# 2-SOM_Interface.net
KiCad netlist of a schematic drawn in Altium Designer
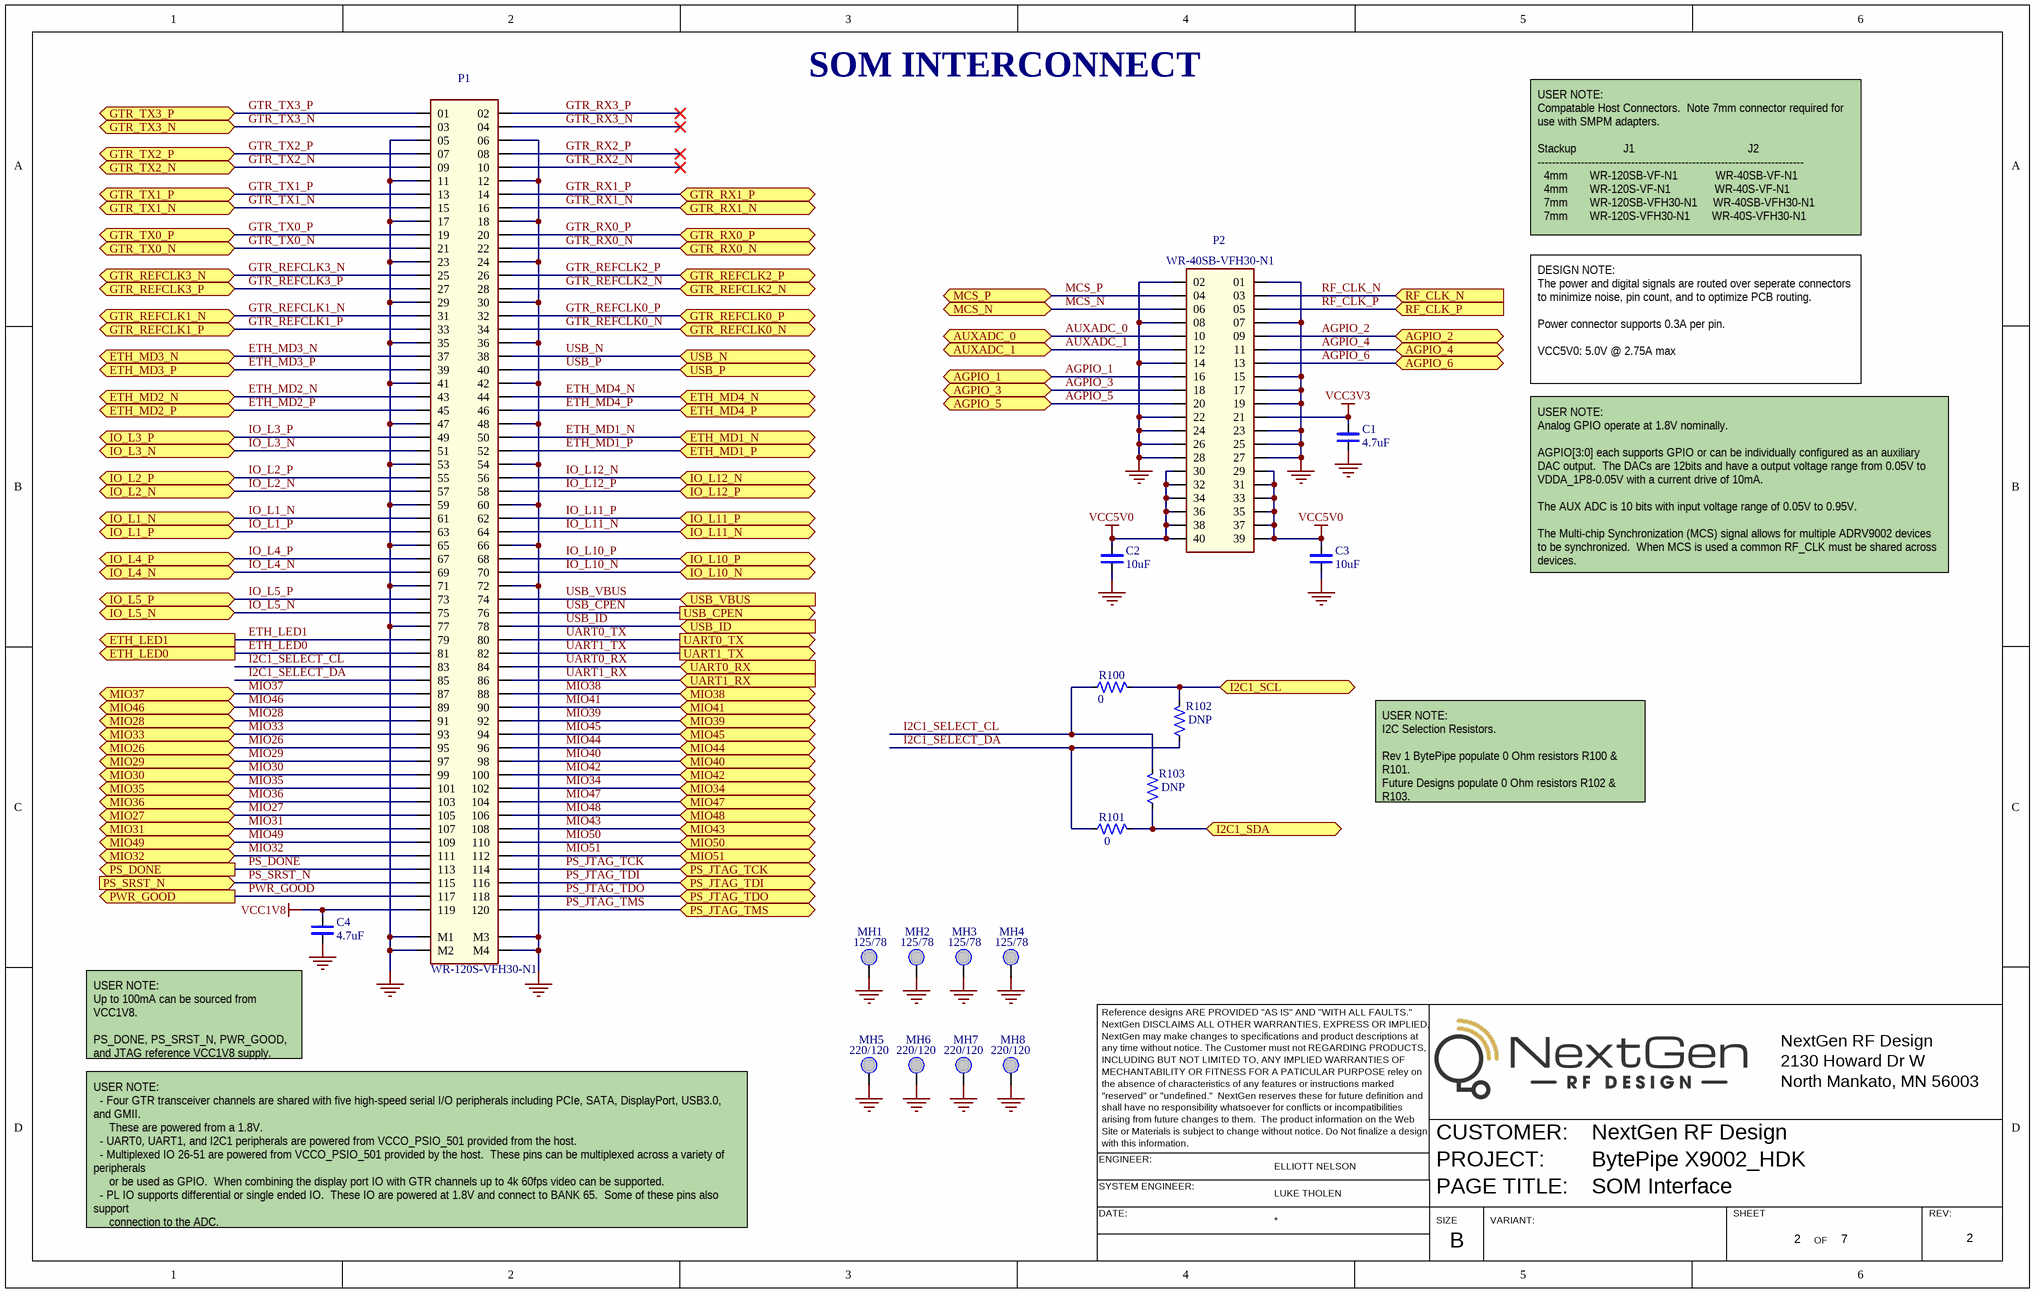
[diagram p0: 2-SOM Interface.SchDoc]

(export (version "E")
  (design (tool "Eeschema 10.0.6"))
  (components
    (comp (ref "C1")
      (value "4.7uF")
      (footprint "SM/0402/CAP")
      (description "CAP CER 4.7UF 10V X5R 0402")
      (fields (field (name "Comment") "CAP_CERAMIC_0402"))
      (libsource (lib "NextGenRF_Symbols_SMT") (part "CAP_CERAMIC_0402"))
    )
    (comp (ref "C2")
      (value "10uF")
      (footprint "SM/0402/CAP")
      (description "10µF ±20% 10V Ceramic Capacitor X5R 0402 (1005 Metric)")
      (fields (field (name "Comment") "CAP_CERAMIC_0402"))
      (libsource (lib "NextGenRF_Symbols_SMT") (part "CAP_CERAMIC_0402"))
    )
    (comp (ref "C3")
      (value "10uF")
      (footprint "SM/0402/CAP")
      (description "10µF ±20% 10V Ceramic Capacitor X5R 0402 (1005 Metric)")
      (fields (field (name "Comment") "CAP_CERAMIC_0402"))
      (libsource (lib "NextGenRF_Symbols_SMT") (part "CAP_CERAMIC_0402"))
    )
    (comp (ref "C4")
      (value "4.7uF")
      (footprint "SM/0402/CAP")
      (description "CAP CER 4.7UF 10V X5R 0402")
      (fields (field (name "Comment") "CAP_CERAMIC_0402"))
      (libsource (lib "NextGenRF_Symbols_SMT") (part "CAP_CERAMIC_0402"))
    )
    (comp (ref "MH1")
      (value "HOLE_PTH_125/78")
      (footprint "NGRF_Mechanical_Footprints:MTG125/78")
      (description "125 mil pad / 78 mil hole")
      (libsource (lib "NextGenRF_Symbols_MECH") (part "HOLE_PTH_125/78"))
    )
    (comp (ref "MH2")
      (value "HOLE_PTH_125/78")
      (footprint "NGRF_Mechanical_Footprints:MTG125/78")
      (description "125 mil pad / 78 mil hole")
      (libsource (lib "NextGenRF_Symbols_MECH") (part "HOLE_PTH_125/78"))
    )
    (comp (ref "MH3")
      (value "HOLE_PTH_125/78")
      (footprint "NGRF_Mechanical_Footprints:MTG125/78")
      (description "125 mil pad / 78 mil hole")
      (libsource (lib "NextGenRF_Symbols_MECH") (part "HOLE_PTH_125/78"))
    )
    (comp (ref "MH4")
      (value "HOLE_PTH_125/78")
      (footprint "NGRF_Mechanical_Footprints:MTG125/78")
      (description "125 mil pad / 78 mil hole")
      (libsource (lib "NextGenRF_Symbols_MECH") (part "HOLE_PTH_125/78"))
    )
    (comp (ref "MH5")
      (value "HOLE_PTH_220/120")
      (footprint "MTG220/120")
      (description "220 mil pad / 120 mil hole (#4 Pan Head Screw)")
      (libsource (lib "NextGenRF_Symbols_MECH") (part "HOLE_PTH_220/120"))
    )
    (comp (ref "MH6")
      (value "HOLE_PTH_220/120")
      (footprint "MTG220/120")
      (description "220 mil pad / 120 mil hole (#4 Pan Head Screw)")
      (libsource (lib "NextGenRF_Symbols_MECH") (part "HOLE_PTH_220/120"))
    )
    (comp (ref "MH7")
      (value "HOLE_PTH_220/120")
      (footprint "MTG220/120")
      (description "220 mil pad / 120 mil hole (#4 Pan Head Screw)")
      (libsource (lib "NextGenRF_Symbols_MECH") (part "HOLE_PTH_220/120"))
    )
    (comp (ref "MH8")
      (value "HOLE_PTH_220/120")
      (footprint "MTG220/120")
      (description "220 mil pad / 120 mil hole (#4 Pan Head Screw)")
      (libsource (lib "NextGenRF_Symbols_MECH") (part "HOLE_PTH_220/120"))
    )
    (comp (ref "P1")
      (value "WR-120S-VFH30-N1")
      (footprint "SM/CON/JAE/WR-120S-VFH30-N1")
      (description "0.5 mm pitch, 120 Position Connector Receptacle, Center Strip Contacts Surface Mount Gold.")
      (fields (field (name "Comment") "WR-120S-VFH30-N1‎"))
      (libsource (lib "NextGenRF_Symbols_SMT") (part "CON_JAE_WR-120S-VFH30-N1"))
    )
    (comp (ref "P2")
      (value "WR-40SB-VFH30-N1")
      (footprint "SM/CON/JAE/WR-40SB-VFH30-N1")
      (fields (field (name "Comment") "WR-40SB-VFH30-N1‎"))
      (libsource (lib "NextGenRF_Symbols_SMT") (part "CON_JAE_WR-40SB-VFH30-N1"))
    )
    (comp (ref "R100")
      (value "0")
      (footprint "SM/0402/RES")
      (description "RES SMD 0 OHM JUMPER 1/10W 0402")
      (fields (field (name "Comment") "RES_0402_A"))
      (libsource (lib "NextGenRF_Symbols_SMT") (part "RES_0402_A"))
    )
    (comp (ref "R101")
      (value "0")
      (footprint "SM/0402/RES")
      (description "RES SMD 0 OHM JUMPER 1/10W 0402")
      (fields (field (name "Comment") "RES_0402_A"))
      (libsource (lib "NextGenRF_Symbols_SMT") (part "RES_0402_A"))
    )
    (comp (ref "R102")
      (value "DNP")
      (footprint "SM/0402/RES")
      (fields (field (name "Comment") "RES_0402_A"))
      (libsource (lib "NextGenRF_Symbols_SMT") (part "RES_0402_A"))
    )
    (comp (ref "R103")
      (value "DNP")
      (footprint "SM/0402/RES")
      (fields (field (name "Comment") "RES_0402_A"))
      (libsource (lib "NextGenRF_Symbols_SMT") (part "RES_0402_A"))
    )
  )
  (nets
    (net (code "1") (name "/AGPIO_1") (class "Default")
      (node (ref "P2") (pin "16") (pinfunction "16_16") (pintype "passive"))
    )
    (net (code "2") (name "/AGPIO_2") (class "Default")
      (node (ref "P2") (pin "09") (pinfunction "09_09") (pintype "passive"))
    )
    (net (code "3") (name "/AGPIO_3") (class "Default")
      (node (ref "P2") (pin "18") (pinfunction "18_18") (pintype "passive"))
    )
    (net (code "4") (name "/AGPIO_4") (class "Default")
      (node (ref "P2") (pin "11") (pinfunction "11_11") (pintype "passive"))
    )
    (net (code "5") (name "/AGPIO_5") (class "Default")
      (node (ref "P2") (pin "20") (pinfunction "20_20") (pintype "passive"))
    )
    (net (code "6") (name "/AGPIO_6") (class "Default")
      (node (ref "P2") (pin "13") (pinfunction "13_13") (pintype "passive"))
    )
    (net (code "7") (name "/AUXADC_0") (class "Default")
      (node (ref "P2") (pin "10") (pinfunction "10_10") (pintype "passive"))
    )
    (net (code "8") (name "/AUXADC_1") (class "Default")
      (node (ref "P2") (pin "12") (pinfunction "12_12") (pintype "passive"))
    )
    (net (code "9") (name "/ETH_LED0") (class "Default")
      (node (ref "P1") (pin "81") (pinfunction "81_81") (pintype "passive"))
    )
    (net (code "10") (name "/ETH_LED1") (class "Default")
      (node (ref "P1") (pin "79") (pinfunction "79_79") (pintype "passive"))
    )
    (net (code "11") (name "/ETH_MD1_N") (class "Default")
      (node (ref "P1") (pin "50") (pinfunction "50_50") (pintype "passive"))
    )
    (net (code "12") (name "/ETH_MD1_P") (class "Default")
      (node (ref "P1") (pin "52") (pinfunction "52_52") (pintype "passive"))
    )
    (net (code "13") (name "/ETH_MD2_N") (class "Default")
      (node (ref "P1") (pin "43") (pinfunction "43_43") (pintype "passive"))
    )
    (net (code "14") (name "/ETH_MD2_P") (class "Default")
      (node (ref "P1") (pin "45") (pinfunction "45_45") (pintype "passive"))
    )
    (net (code "15") (name "/ETH_MD3_N") (class "Default")
      (node (ref "P1") (pin "37") (pinfunction "37_37") (pintype "passive"))
    )
    (net (code "16") (name "/ETH_MD3_P") (class "Default")
      (node (ref "P1") (pin "39") (pinfunction "39_39") (pintype "passive"))
    )
    (net (code "17") (name "/ETH_MD4_N") (class "Default")
      (node (ref "P1") (pin "44") (pinfunction "44_44") (pintype "passive"))
    )
    (net (code "18") (name "/ETH_MD4_P") (class "Default")
      (node (ref "P1") (pin "46") (pinfunction "46_46") (pintype "passive"))
    )
    (net (code "19") (name "/GTR_REFCLK0_N") (class "Default")
      (node (ref "P1") (pin "34") (pinfunction "34_34") (pintype "passive"))
    )
    (net (code "20") (name "/GTR_REFCLK0_P") (class "Default")
      (node (ref "P1") (pin "32") (pinfunction "32_32") (pintype "passive"))
    )
    (net (code "21") (name "/GTR_REFCLK1_N") (class "Default")
      (node (ref "P1") (pin "31") (pinfunction "31_31") (pintype "passive"))
    )
    (net (code "22") (name "/GTR_REFCLK1_P") (class "Default")
      (node (ref "P1") (pin "33") (pinfunction "33_33") (pintype "passive"))
    )
    (net (code "23") (name "/GTR_REFCLK2_N") (class "Default")
      (node (ref "P1") (pin "28") (pinfunction "28_28") (pintype "passive"))
    )
    (net (code "24") (name "/GTR_REFCLK2_P") (class "Default")
      (node (ref "P1") (pin "26") (pinfunction "26_26") (pintype "passive"))
    )
    (net (code "25") (name "/GTR_REFCLK3_N") (class "Default")
      (node (ref "P1") (pin "25") (pinfunction "25_25") (pintype "passive"))
    )
    (net (code "26") (name "/GTR_REFCLK3_P") (class "Default")
      (node (ref "P1") (pin "27") (pinfunction "27_27") (pintype "passive"))
    )
    (net (code "27") (name "/GTR_RX0_N") (class "Default")
      (node (ref "P1") (pin "22") (pinfunction "22_22") (pintype "passive"))
    )
    (net (code "28") (name "/GTR_RX0_P") (class "Default")
      (node (ref "P1") (pin "20") (pinfunction "20_20") (pintype "passive"))
    )
    (net (code "29") (name "/GTR_RX1_N") (class "Default")
      (node (ref "P1") (pin "16") (pinfunction "16_16") (pintype "passive"))
    )
    (net (code "30") (name "/GTR_RX1_P") (class "Default")
      (node (ref "P1") (pin "14") (pinfunction "14_14") (pintype "passive"))
    )
    (net (code "31") (name "/GTR_RX2_N") (class "Default")
      (node (ref "P1") (pin "10") (pinfunction "10_10") (pintype "passive+no_connect"))
    )
    (net (code "32") (name "/GTR_RX2_P") (class "Default")
      (node (ref "P1") (pin "08") (pinfunction "08_08") (pintype "passive+no_connect"))
    )
    (net (code "33") (name "/GTR_RX3_N") (class "Default")
      (node (ref "P1") (pin "04") (pinfunction "04_04") (pintype "passive+no_connect"))
    )
    (net (code "34") (name "/GTR_RX3_P") (class "Default")
      (node (ref "P1") (pin "02") (pinfunction "02_02") (pintype "passive+no_connect"))
    )
    (net (code "35") (name "/GTR_TX0_N") (class "Default")
      (node (ref "P1") (pin "21") (pinfunction "21_21") (pintype "passive"))
    )
    (net (code "36") (name "/GTR_TX0_P") (class "Default")
      (node (ref "P1") (pin "19") (pinfunction "19_19") (pintype "passive"))
    )
    (net (code "37") (name "/GTR_TX1_N") (class "Default")
      (node (ref "P1") (pin "15") (pinfunction "15_15") (pintype "passive"))
    )
    (net (code "38") (name "/GTR_TX1_P") (class "Default")
      (node (ref "P1") (pin "13") (pinfunction "13_13") (pintype "passive"))
    )
    (net (code "39") (name "/GTR_TX2_N") (class "Default")
      (node (ref "P1") (pin "09") (pinfunction "09_09") (pintype "passive"))
    )
    (net (code "40") (name "/GTR_TX2_P") (class "Default")
      (node (ref "P1") (pin "07") (pinfunction "07_07") (pintype "passive"))
    )
    (net (code "41") (name "/GTR_TX3_N") (class "Default")
      (node (ref "P1") (pin "03") (pinfunction "03_03") (pintype "passive"))
    )
    (net (code "42") (name "/GTR_TX3_P") (class "Default")
      (node (ref "P1") (pin "01") (pinfunction "01_01") (pintype "passive"))
    )
    (net (code "43") (name "/I2C1_SCL") (class "Default")
      (node (ref "R100") (pin "1") (pinfunction "1_1") (pintype "passive"))
      (node (ref "R102") (pin "1") (pinfunction "1_1") (pintype "passive"))
    )
    (net (code "44") (name "/I2C1_SDA") (class "Default")
      (node (ref "R101") (pin "1") (pinfunction "1_1") (pintype "passive"))
      (node (ref "R103") (pin "2") (pinfunction "2_2") (pintype "passive"))
    )
    (net (code "45") (name "/I2C1_SELECT_CL") (class "Default")
      (node (ref "P1") (pin "83") (pinfunction "83_83") (pintype "passive"))
      (node (ref "R100") (pin "2") (pinfunction "2_2") (pintype "passive"))
      (node (ref "R103") (pin "1") (pinfunction "1_1") (pintype "passive"))
    )
    (net (code "46") (name "/I2C1_SELECT_DA") (class "Default")
      (node (ref "P1") (pin "85") (pinfunction "85_85") (pintype "passive"))
      (node (ref "R101") (pin "2") (pinfunction "2_2") (pintype "passive"))
      (node (ref "R102") (pin "2") (pinfunction "2_2") (pintype "passive"))
    )
    (net (code "47") (name "/IO_L1_N") (class "Default")
      (node (ref "P1") (pin "61") (pinfunction "61_61") (pintype "passive"))
    )
    (net (code "48") (name "/IO_L1_P") (class "Default")
      (node (ref "P1") (pin "63") (pinfunction "63_63") (pintype "passive"))
    )
    (net (code "49") (name "/IO_L2_N") (class "Default")
      (node (ref "P1") (pin "57") (pinfunction "57_57") (pintype "passive"))
    )
    (net (code "50") (name "/IO_L2_P") (class "Default")
      (node (ref "P1") (pin "55") (pinfunction "55_55") (pintype "passive"))
    )
    (net (code "51") (name "/IO_L3_N") (class "Default")
      (node (ref "P1") (pin "51") (pinfunction "51_51") (pintype "passive"))
    )
    (net (code "52") (name "/IO_L3_P") (class "Default")
      (node (ref "P1") (pin "49") (pinfunction "49_49") (pintype "passive"))
    )
    (net (code "53") (name "/IO_L4_N") (class "Default")
      (node (ref "P1") (pin "69") (pinfunction "69_69") (pintype "passive"))
    )
    (net (code "54") (name "/IO_L4_P") (class "Default")
      (node (ref "P1") (pin "67") (pinfunction "67_67") (pintype "passive"))
    )
    (net (code "55") (name "/IO_L5_N") (class "Default")
      (node (ref "P1") (pin "75") (pinfunction "75_75") (pintype "passive"))
    )
    (net (code "56") (name "/IO_L5_P") (class "Default")
      (node (ref "P1") (pin "73") (pinfunction "73_73") (pintype "passive"))
    )
    (net (code "57") (name "/IO_L10_N") (class "Default")
      (node (ref "P1") (pin "70") (pinfunction "70_70") (pintype "passive"))
    )
    (net (code "58") (name "/IO_L10_P") (class "Default")
      (node (ref "P1") (pin "68") (pinfunction "68_68") (pintype "passive"))
    )
    (net (code "59") (name "/IO_L11_N") (class "Default")
      (node (ref "P1") (pin "64") (pinfunction "64_64") (pintype "passive"))
    )
    (net (code "60") (name "/IO_L11_P") (class "Default")
      (node (ref "P1") (pin "62") (pinfunction "62_62") (pintype "passive"))
    )
    (net (code "61") (name "/IO_L12_N") (class "Default")
      (node (ref "P1") (pin "56") (pinfunction "56_56") (pintype "passive"))
    )
    (net (code "62") (name "/IO_L12_P") (class "Default")
      (node (ref "P1") (pin "58") (pinfunction "58_58") (pintype "passive"))
    )
    (net (code "63") (name "/MCS_N") (class "Default")
      (node (ref "P2") (pin "06") (pinfunction "06_06") (pintype "passive"))
    )
    (net (code "64") (name "/MCS_P") (class "Default")
      (node (ref "P2") (pin "04") (pinfunction "04_04") (pintype "passive"))
    )
    (net (code "65") (name "/MIO26") (class "Default")
      (node (ref "P1") (pin "95") (pinfunction "95_95") (pintype "passive"))
    )
    (net (code "66") (name "/MIO27") (class "Default")
      (node (ref "P1") (pin "105") (pinfunction "105_105") (pintype "passive"))
    )
    (net (code "67") (name "/MIO28") (class "Default")
      (node (ref "P1") (pin "91") (pinfunction "91_91") (pintype "passive"))
    )
    (net (code "68") (name "/MIO29") (class "Default")
      (node (ref "P1") (pin "97") (pinfunction "97_97") (pintype "passive"))
    )
    (net (code "69") (name "/MIO30") (class "Default")
      (node (ref "P1") (pin "99") (pinfunction "99_99") (pintype "passive"))
    )
    (net (code "70") (name "/MIO31") (class "Default")
      (node (ref "P1") (pin "107") (pinfunction "107_107") (pintype "passive"))
    )
    (net (code "71") (name "/MIO32") (class "Default")
      (node (ref "P1") (pin "111") (pinfunction "111_111") (pintype "passive"))
    )
    (net (code "72") (name "/MIO33") (class "Default")
      (node (ref "P1") (pin "93") (pinfunction "93_93") (pintype "passive"))
    )
    (net (code "73") (name "/MIO34") (class "Default")
      (node (ref "P1") (pin "102") (pinfunction "102_102") (pintype "passive"))
    )
    (net (code "74") (name "/MIO35") (class "Default")
      (node (ref "P1") (pin "101") (pinfunction "101_101") (pintype "passive"))
    )
    (net (code "75") (name "/MIO36") (class "Default")
      (node (ref "P1") (pin "103") (pinfunction "103_103") (pintype "passive"))
    )
    (net (code "76") (name "/MIO37") (class "Default")
      (node (ref "P1") (pin "87") (pinfunction "87_87") (pintype "passive"))
    )
    (net (code "77") (name "/MIO38") (class "Default")
      (node (ref "P1") (pin "88") (pinfunction "88_88") (pintype "passive"))
    )
    (net (code "78") (name "/MIO39") (class "Default")
      (node (ref "P1") (pin "92") (pinfunction "92_92") (pintype "passive"))
    )
    (net (code "79") (name "/MIO40") (class "Default")
      (node (ref "P1") (pin "98") (pinfunction "98_98") (pintype "passive"))
    )
    (net (code "80") (name "/MIO41") (class "Default")
      (node (ref "P1") (pin "90") (pinfunction "90_90") (pintype "passive"))
    )
    (net (code "81") (name "/MIO42") (class "Default")
      (node (ref "P1") (pin "100") (pinfunction "100_100") (pintype "passive"))
    )
    (net (code "82") (name "/MIO43") (class "Default")
      (node (ref "P1") (pin "108") (pinfunction "108_108") (pintype "passive"))
    )
    (net (code "83") (name "/MIO44") (class "Default")
      (node (ref "P1") (pin "96") (pinfunction "96_96") (pintype "passive"))
    )
    (net (code "84") (name "/MIO45") (class "Default")
      (node (ref "P1") (pin "94") (pinfunction "94_94") (pintype "passive"))
    )
    (net (code "85") (name "/MIO46") (class "Default")
      (node (ref "P1") (pin "89") (pinfunction "89_89") (pintype "passive"))
    )
    (net (code "86") (name "/MIO47") (class "Default")
      (node (ref "P1") (pin "104") (pinfunction "104_104") (pintype "passive"))
    )
    (net (code "87") (name "/MIO48") (class "Default")
      (node (ref "P1") (pin "106") (pinfunction "106_106") (pintype "passive"))
    )
    (net (code "88") (name "/MIO49") (class "Default")
      (node (ref "P1") (pin "109") (pinfunction "109_109") (pintype "passive"))
    )
    (net (code "89") (name "/MIO50") (class "Default")
      (node (ref "P1") (pin "110") (pinfunction "110_110") (pintype "passive"))
    )
    (net (code "90") (name "/MIO51") (class "Default")
      (node (ref "P1") (pin "112") (pinfunction "112_112") (pintype "passive"))
    )
    (net (code "91") (name "/PS_DONE") (class "Default")
      (node (ref "P1") (pin "113") (pinfunction "113_113") (pintype "passive"))
    )
    (net (code "92") (name "/PS_JTAG_TCK") (class "Default")
      (node (ref "P1") (pin "114") (pinfunction "114_114") (pintype "passive"))
    )
    (net (code "93") (name "/PS_JTAG_TDI") (class "Default")
      (node (ref "P1") (pin "116") (pinfunction "116_116") (pintype "passive"))
    )
    (net (code "94") (name "/PS_JTAG_TDO") (class "Default")
      (node (ref "P1") (pin "118") (pinfunction "118_118") (pintype "passive"))
    )
    (net (code "95") (name "/PS_JTAG_TMS") (class "Default")
      (node (ref "P1") (pin "120") (pinfunction "120_120") (pintype "passive"))
    )
    (net (code "96") (name "/PS_SRST_N") (class "Default")
      (node (ref "P1") (pin "115") (pinfunction "115_115") (pintype "passive"))
    )
    (net (code "97") (name "/PWR_GOOD") (class "Default")
      (node (ref "P1") (pin "117") (pinfunction "117_117") (pintype "passive"))
    )
    (net (code "98") (name "/RF_CLK_N") (class "Default")
      (node (ref "P2") (pin "03") (pinfunction "03_03") (pintype "passive"))
    )
    (net (code "99") (name "/RF_CLK_P") (class "Default")
      (node (ref "P2") (pin "05") (pinfunction "05_05") (pintype "passive"))
    )
    (net (code "100") (name "/UART0_RX") (class "Default")
      (node (ref "P1") (pin "84") (pinfunction "84_84") (pintype "passive"))
    )
    (net (code "101") (name "/UART0_TX") (class "Default")
      (node (ref "P1") (pin "80") (pinfunction "80_80") (pintype "passive"))
    )
    (net (code "102") (name "/UART1_RX") (class "Default")
      (node (ref "P1") (pin "86") (pinfunction "86_86") (pintype "passive"))
    )
    (net (code "103") (name "/UART1_TX") (class "Default")
      (node (ref "P1") (pin "82") (pinfunction "82_82") (pintype "passive"))
    )
    (net (code "104") (name "/USB_CPEN") (class "Default")
      (node (ref "P1") (pin "76") (pinfunction "76_76") (pintype "passive"))
    )
    (net (code "105") (name "/USB_ID") (class "Default")
      (node (ref "P1") (pin "78") (pinfunction "78_78") (pintype "passive"))
    )
    (net (code "106") (name "/USB_N") (class "Default")
      (node (ref "P1") (pin "38") (pinfunction "38_38") (pintype "passive"))
    )
    (net (code "107") (name "/USB_P") (class "Default")
      (node (ref "P1") (pin "40") (pinfunction "40_40") (pintype "passive"))
    )
    (net (code "108") (name "/USB_VBUS") (class "Default")
      (node (ref "P1") (pin "74") (pinfunction "74_74") (pintype "passive"))
    )
    (net (code "109") (name "GND") (class "Default")
      (node (ref "C1") (pin "2") (pinfunction "N2_2") (pintype "passive"))
      (node (ref "C2") (pin "2") (pinfunction "N2_2") (pintype "passive"))
      (node (ref "C3") (pin "2") (pinfunction "N2_2") (pintype "passive"))
      (node (ref "C4") (pin "2") (pinfunction "N2_2") (pintype "passive"))
      (node (ref "MH1") (pin "1") (pinfunction "N1_1") (pintype "passive"))
      (node (ref "MH2") (pin "1") (pinfunction "N1_1") (pintype "passive"))
      (node (ref "MH3") (pin "1") (pinfunction "N1_1") (pintype "passive"))
      (node (ref "MH4") (pin "1") (pinfunction "N1_1") (pintype "passive"))
      (node (ref "MH5") (pin "1") (pinfunction "N1_1") (pintype "passive"))
      (node (ref "MH6") (pin "1") (pinfunction "N1_1") (pintype "passive"))
      (node (ref "MH7") (pin "1") (pinfunction "N1_1") (pintype "passive"))
      (node (ref "MH8") (pin "1") (pinfunction "N1_1") (pintype "passive"))
      (node (ref "P1") (pin "05") (pinfunction "05_05") (pintype "passive"))
      (node (ref "P1") (pin "06") (pinfunction "06_06") (pintype "passive"))
      (node (ref "P1") (pin "11") (pinfunction "11_11") (pintype "passive"))
      (node (ref "P1") (pin "12") (pinfunction "12_12") (pintype "passive"))
      (node (ref "P1") (pin "17") (pinfunction "17_17") (pintype "passive"))
      (node (ref "P1") (pin "18") (pinfunction "18_18") (pintype "passive"))
      (node (ref "P1") (pin "23") (pinfunction "23_23") (pintype "passive"))
      (node (ref "P1") (pin "24") (pinfunction "24_24") (pintype "passive"))
      (node (ref "P1") (pin "29") (pinfunction "29_29") (pintype "passive"))
      (node (ref "P1") (pin "30") (pinfunction "30_30") (pintype "passive"))
      (node (ref "P1") (pin "35") (pinfunction "35_35") (pintype "passive"))
      (node (ref "P1") (pin "36") (pinfunction "36_36") (pintype "passive"))
      (node (ref "P1") (pin "41") (pinfunction "41_41") (pintype "passive"))
      (node (ref "P1") (pin "42") (pinfunction "42_42") (pintype "passive"))
      (node (ref "P1") (pin "47") (pinfunction "47_47") (pintype "passive"))
      (node (ref "P1") (pin "48") (pinfunction "48_48") (pintype "passive"))
      (node (ref "P1") (pin "53") (pinfunction "53_53") (pintype "passive"))
      (node (ref "P1") (pin "54") (pinfunction "54_54") (pintype "passive"))
      (node (ref "P1") (pin "59") (pinfunction "59_59") (pintype "passive"))
      (node (ref "P1") (pin "60") (pinfunction "60_60") (pintype "passive"))
      (node (ref "P1") (pin "65") (pinfunction "65_65") (pintype "passive"))
      (node (ref "P1") (pin "66") (pinfunction "66_66") (pintype "passive"))
      (node (ref "P1") (pin "71") (pinfunction "71_71") (pintype "passive"))
      (node (ref "P1") (pin "72") (pinfunction "72_72") (pintype "passive"))
      (node (ref "P1") (pin "77") (pinfunction "77_77") (pintype "passive"))
      (node (ref "P1") (pin "M1") (pinfunction "M1_M1") (pintype "passive"))
      (node (ref "P1") (pin "M2") (pinfunction "M2_M2") (pintype "passive"))
      (node (ref "P1") (pin "M3") (pinfunction "M3_M3") (pintype "passive"))
      (node (ref "P1") (pin "M4") (pinfunction "M4_M4") (pintype "passive"))
      (node (ref "P2") (pin "01") (pinfunction "01_01") (pintype "passive"))
      (node (ref "P2") (pin "02") (pinfunction "02_02") (pintype "passive"))
      (node (ref "P2") (pin "07") (pinfunction "07_07") (pintype "passive"))
      (node (ref "P2") (pin "08") (pinfunction "08_08") (pintype "passive"))
      (node (ref "P2") (pin "14") (pinfunction "14_14") (pintype "passive"))
      (node (ref "P2") (pin "15") (pinfunction "15_15") (pintype "passive"))
      (node (ref "P2") (pin "17") (pinfunction "17_17") (pintype "passive"))
      (node (ref "P2") (pin "19") (pinfunction "19_19") (pintype "passive"))
      (node (ref "P2") (pin "22") (pinfunction "22_22") (pintype "passive"))
      (node (ref "P2") (pin "23") (pinfunction "23_23") (pintype "passive"))
      (node (ref "P2") (pin "24") (pinfunction "24_24") (pintype "passive"))
      (node (ref "P2") (pin "25") (pinfunction "25_25") (pintype "passive"))
      (node (ref "P2") (pin "26") (pinfunction "26_26") (pintype "passive"))
      (node (ref "P2") (pin "27") (pinfunction "27_27") (pintype "passive"))
      (node (ref "P2") (pin "28") (pinfunction "28_28") (pintype "passive"))
    )
    (net (code "110") (name "VCC1V8") (class "Default")
      (node (ref "C4") (pin "1") (pinfunction "N1_1") (pintype "passive"))
      (node (ref "P1") (pin "119") (pinfunction "119_119") (pintype "passive"))
    )
    (net (code "111") (name "VCC3V3") (class "Default")
      (node (ref "C1") (pin "1") (pinfunction "N1_1") (pintype "passive"))
      (node (ref "P2") (pin "21") (pinfunction "21_21") (pintype "passive"))
    )
    (net (code "112") (name "VCC5V0") (class "Default")
      (node (ref "C2") (pin "1") (pinfunction "N1_1") (pintype "passive"))
      (node (ref "C3") (pin "1") (pinfunction "N1_1") (pintype "passive"))
      (node (ref "P2") (pin "29") (pinfunction "29_29") (pintype "passive"))
      (node (ref "P2") (pin "30") (pinfunction "30_30") (pintype "passive"))
      (node (ref "P2") (pin "31") (pinfunction "31_31") (pintype "passive"))
      (node (ref "P2") (pin "32") (pinfunction "32_32") (pintype "passive"))
      (node (ref "P2") (pin "33") (pinfunction "33_33") (pintype "passive"))
      (node (ref "P2") (pin "34") (pinfunction "34_34") (pintype "passive"))
      (node (ref "P2") (pin "35") (pinfunction "35_35") (pintype "passive"))
      (node (ref "P2") (pin "36") (pinfunction "36_36") (pintype "passive"))
      (node (ref "P2") (pin "37") (pinfunction "37_37") (pintype "passive"))
      (node (ref "P2") (pin "38") (pinfunction "38_38") (pintype "passive"))
      (node (ref "P2") (pin "39") (pinfunction "39_39") (pintype "passive"))
      (node (ref "P2") (pin "40") (pinfunction "40_40") (pintype "passive"))
    )
  )
)
